# KeyBesselEsquematico.net
KiCad netlist of a schematic drawn in Altium Designer
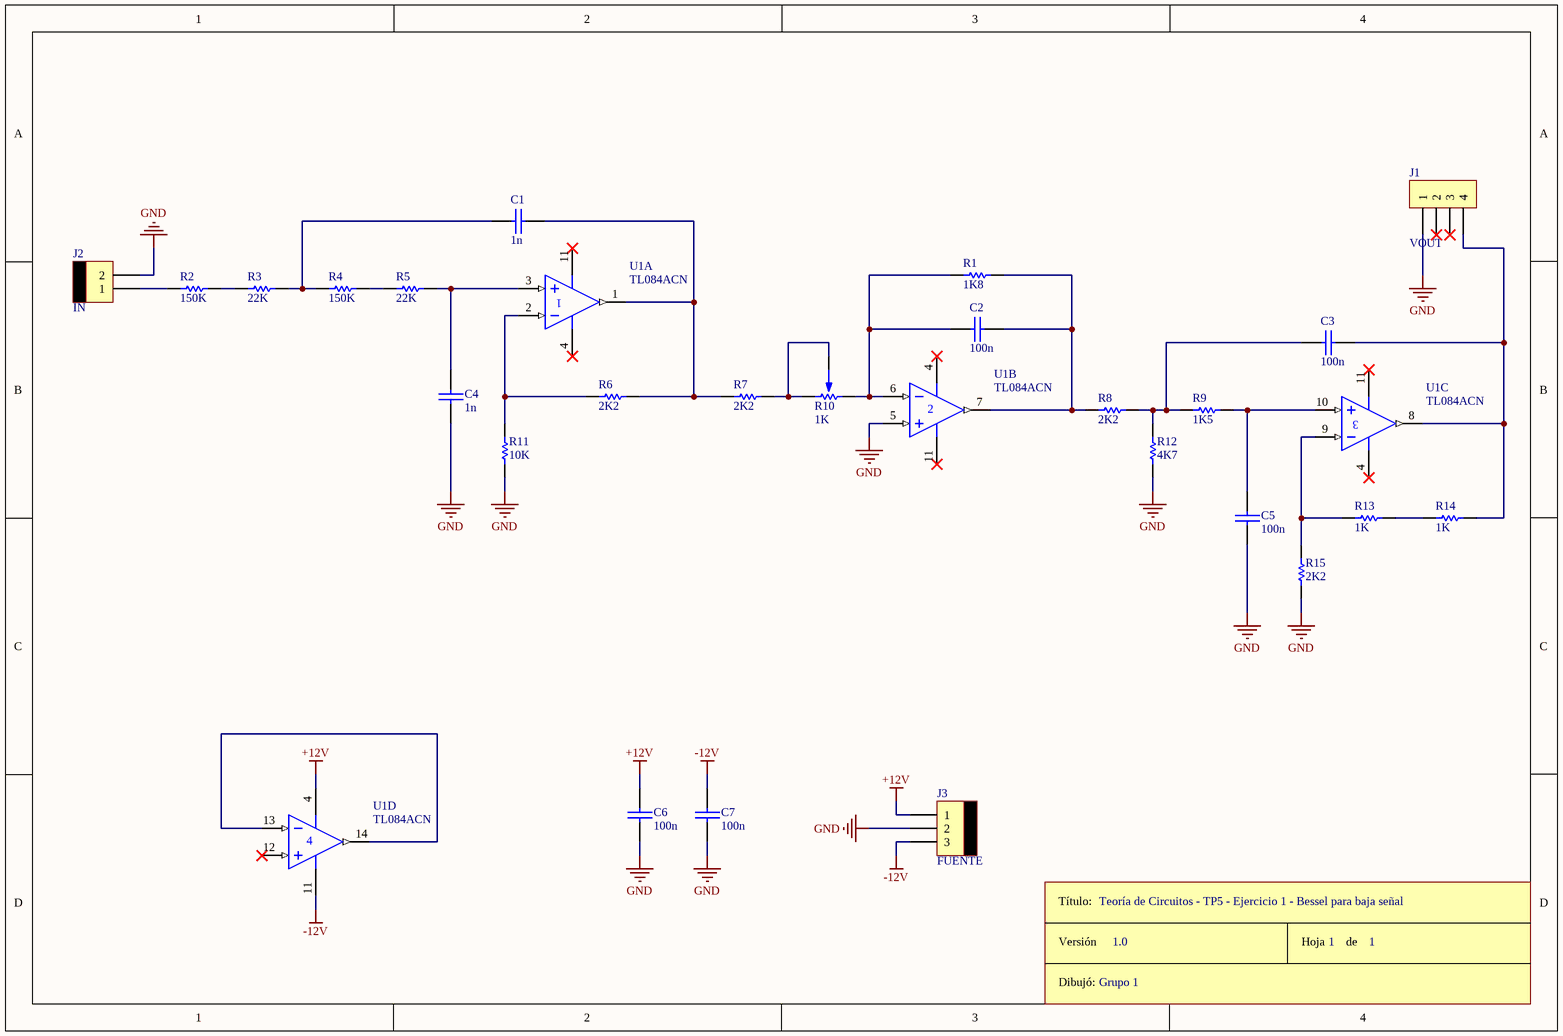
[diagram p0: KeyBesselEsquematico.SchDoc]

(export (version "E")
  (design (tool "Eeschema 10.0.6"))
  (components
    (comp (ref "C1") (value "1n") (footprint "CAP100") (libsource (lib "LIBEBAL") (part "CAP")))
    (comp (ref "C2") (value "100n") (footprint "CAP100") (libsource (lib "LIBEBAL") (part "CAP")))
    (comp (ref "C3") (value "100n") (footprint "CAP100") (libsource (lib "LIBEBAL") (part "CAP")))
    (comp (ref "C4") (value "1n") (footprint "CAP100") (libsource (lib "LIBEBAL") (part "CAP")))
    (comp (ref "C5") (value "100n") (footprint "CAP100") (libsource (lib "LIBEBAL") (part "CAP")))
    (comp (ref "C6") (value "100n") (footprint "CAP100") (libsource (lib "LIBEBAL") (part "CAP")))
    (comp (ref "C7") (value "100n") (footprint "CAP100") (libsource (lib "LIBEBAL") (part "CAP")))
    (comp (ref "J1") (value "VOUT") (footprint "SIP4") (libsource (lib "LIBEBAL") (part "CON4")))
    (comp (ref "J2") (value "IN") (footprint "MOLEX2") (libsource (lib "LIBEBAL") (part "MOLEX2")))
    (comp (ref "J3") (value "FUENTE") (footprint "MOLEX3") (libsource (lib "LIBEBAL") (part "MOLEX3")))
    (comp (ref "R1") (value "1K8") (footprint "RES300") (libsource (lib "LIBEBAL") (part "RES")))
    (comp (ref "R2") (value "150K") (footprint "RES300") (libsource (lib "LIBEBAL") (part "RES")))
    (comp (ref "R3") (value "22K") (footprint "RES300") (libsource (lib "LIBEBAL") (part "RES")))
    (comp (ref "R4") (value "150K") (footprint "RES300") (libsource (lib "LIBEBAL") (part "RES")))
    (comp (ref "R5") (value "22K") (footprint "RES300") (libsource (lib "LIBEBAL") (part "RES")))
    (comp (ref "R6") (value "2K2") (footprint "RES300") (libsource (lib "LIBEBAL") (part "RES")))
    (comp (ref "R7") (value "2K2") (footprint "RES300") (libsource (lib "LIBEBAL") (part "RES")))
    (comp (ref "R8") (value "2K2") (footprint "RES300") (libsource (lib "LIBEBAL") (part "RES")))
    (comp (ref "R9") (value "1K5") (footprint "RES300") (libsource (lib "LIBEBAL") (part "RES")))
    (comp (ref "R10") (value "1K") (footprint "PRESET V") (libsource (lib "LIBEBAL") (part "PRESET")))
    (comp (ref "R11") (value "10K") (footprint "RES300") (libsource (lib "LIBEBAL") (part "RES")))
    (comp (ref "R12") (value "4K7") (footprint "RES300") (libsource (lib "LIBEBAL") (part "RES")))
    (comp (ref "R13") (value "1K") (footprint "RES300") (libsource (lib "LIBEBAL") (part "RES")))
    (comp (ref "R14") (value "1K") (footprint "RES300") (libsource (lib "LIBEBAL") (part "RES")))
    (comp (ref "R15") (value "2K2") (footprint "RES300") (libsource (lib "LIBEBAL") (part "RES")))
    (comp (ref "ROT1") (value "Rótulo") (libsource (lib "LIB PIO IX") (part "Rótulo")))
    (comp (ref "U1")
      (value "TL084ACN")
      (footprint "646-06")
      (description "JFET-Input Operational Amplifier")
      (fields (field (name "PUBLISHER") "Altium Limited"))
      (libsource (lib "Motorola Amplifier Operational Amplifier") (part "TL084ACN"))
    )
  )
  (nets
    (net (code "1") (name "+12V") (class "Default")
      (node (ref "C6") (pin "1") (pinfunction "1_1") (pintype "passive"))
      (node (ref "J3") (pin "1") (pinfunction "1_1") (pintype "passive"))
      (node (ref "U1") (pin "4") (pinfunction "V+_4") (pintype "power_in"))
    )
    (net (code "2") (name "-12V") (class "Default")
      (node (ref "C7") (pin "1") (pinfunction "1_1") (pintype "passive"))
      (node (ref "J3") (pin "3") (pinfunction "3_3") (pintype "passive"))
      (node (ref "U1") (pin "11") (pinfunction "V-_11") (pintype "power_in"))
    )
    (net (code "3") (name "GND") (class "Default")
      (node (ref "C4") (pin "2") (pinfunction "2_2") (pintype "passive"))
      (node (ref "C5") (pin "2") (pinfunction "2_2") (pintype "passive"))
      (node (ref "C6") (pin "2") (pinfunction "2_2") (pintype "passive"))
      (node (ref "C7") (pin "2") (pinfunction "2_2") (pintype "passive"))
      (node (ref "J1") (pin "1") (pinfunction "1_1") (pintype "passive"))
      (node (ref "J2") (pin "2") (pinfunction "2_2") (pintype "passive"))
      (node (ref "J3") (pin "2") (pinfunction "2_2") (pintype "passive"))
      (node (ref "R11") (pin "1") (pinfunction "1_1") (pintype "passive"))
      (node (ref "R12") (pin "1") (pinfunction "1_1") (pintype "passive"))
      (node (ref "R15") (pin "1") (pinfunction "1_1") (pintype "passive"))
      (node (ref "U1") (pin "5") (pinfunction "IN+_5") (pintype "input"))
    )
    (net (code "4") (name "Net-(C1-Pad1)") (class "Default")
      (node (ref "C1") (pin "1") (pinfunction "1_1") (pintype "passive"))
      (node (ref "R3") (pin "2") (pinfunction "2_2") (pintype "passive"))
      (node (ref "R4") (pin "1") (pinfunction "1_1") (pintype "passive"))
    )
    (net (code "5") (name "Net-(C3-Pad1)") (class "Default")
      (node (ref "C3") (pin "1") (pinfunction "1_1") (pintype "passive"))
      (node (ref "R12") (pin "2") (pinfunction "2_2") (pintype "passive"))
      (node (ref "R8") (pin "2") (pinfunction "2_2") (pintype "passive"))
      (node (ref "R9") (pin "1") (pinfunction "1_1") (pintype "passive"))
    )
    (net (code "6") (name "Net-(J2-Pad1)") (class "Default")
      (node (ref "J2") (pin "1") (pinfunction "1_1") (pintype "passive"))
      (node (ref "R2") (pin "1") (pinfunction "1_1") (pintype "passive"))
    )
    (net (code "7") (name "Net-(R2-Pad2)") (class "Default")
      (node (ref "R2") (pin "2") (pinfunction "2_2") (pintype "passive"))
      (node (ref "R3") (pin "1") (pinfunction "1_1") (pintype "passive"))
    )
    (net (code "8") (name "Net-(R4-Pad2)") (class "Default")
      (node (ref "R4") (pin "2") (pinfunction "2_2") (pintype "passive"))
      (node (ref "R5") (pin "1") (pinfunction "1_1") (pintype "passive"))
    )
    (net (code "9") (name "Net-(R10-Pad1)") (class "Default")
      (node (ref "R10") (pin "1") (pinfunction "1_1") (pintype "passive"))
      (node (ref "R10") (pin "2") (pinfunction "2_2") (pintype "passive"))
      (node (ref "R7") (pin "2") (pinfunction "2_2") (pintype "passive"))
    )
    (net (code "10") (name "Net-(R13-Pad2)") (class "Default")
      (node (ref "R13") (pin "2") (pinfunction "2_2") (pintype "passive"))
      (node (ref "R14") (pin "1") (pinfunction "1_1") (pintype "passive"))
    )
    (net (code "11") (name "Net-(U1A-IN+)") (class "Default")
      (node (ref "C4") (pin "1") (pinfunction "1_1") (pintype "passive"))
      (node (ref "R5") (pin "2") (pinfunction "2_2") (pintype "passive"))
      (node (ref "U1") (pin "3") (pinfunction "IN+_3") (pintype "input"))
    )
    (net (code "12") (name "Net-(U1A-IN-)") (class "Default")
      (node (ref "R11") (pin "2") (pinfunction "2_2") (pintype "passive"))
      (node (ref "R6") (pin "1") (pinfunction "1_1") (pintype "passive"))
      (node (ref "U1") (pin "2") (pinfunction "IN-_2") (pintype "input"))
    )
    (net (code "13") (name "Net-(U1A-OUT)") (class "Default")
      (node (ref "C1") (pin "2") (pinfunction "2_2") (pintype "passive"))
      (node (ref "R6") (pin "2") (pinfunction "2_2") (pintype "passive"))
      (node (ref "R7") (pin "1") (pinfunction "1_1") (pintype "passive"))
      (node (ref "U1") (pin "1") (pinfunction "OUT_1") (pintype "output"))
    )
    (net (code "14") (name "Net-(U1B-IN-)") (class "Default")
      (node (ref "C2") (pin "1") (pinfunction "1_1") (pintype "passive"))
      (node (ref "R1") (pin "1") (pinfunction "1_1") (pintype "passive"))
      (node (ref "R10") (pin "3") (pinfunction "3_3") (pintype "passive"))
      (node (ref "U1") (pin "6") (pinfunction "IN-_6") (pintype "input"))
    )
    (net (code "15") (name "Net-(U1B-OUT)") (class "Default")
      (node (ref "C2") (pin "2") (pinfunction "2_2") (pintype "passive"))
      (node (ref "R1") (pin "2") (pinfunction "2_2") (pintype "passive"))
      (node (ref "R8") (pin "1") (pinfunction "1_1") (pintype "passive"))
      (node (ref "U1") (pin "7") (pinfunction "OUT_7") (pintype "output"))
    )
    (net (code "16") (name "Net-(U1C-IN+)") (class "Default")
      (node (ref "C5") (pin "1") (pinfunction "1_1") (pintype "passive"))
      (node (ref "R9") (pin "2") (pinfunction "2_2") (pintype "passive"))
      (node (ref "U1") (pin "10") (pinfunction "IN+_10") (pintype "input"))
    )
    (net (code "17") (name "Net-(U1C-IN-)") (class "Default")
      (node (ref "R13") (pin "1") (pinfunction "1_1") (pintype "passive"))
      (node (ref "R15") (pin "2") (pinfunction "2_2") (pintype "passive"))
      (node (ref "U1") (pin "9") (pinfunction "IN-_9") (pintype "input"))
    )
    (net (code "18") (name "Net-(U1C-OUT)") (class "Default")
      (node (ref "C3") (pin "2") (pinfunction "2_2") (pintype "passive"))
      (node (ref "J1") (pin "4") (pinfunction "4_4") (pintype "passive"))
      (node (ref "R14") (pin "2") (pinfunction "2_2") (pintype "passive"))
      (node (ref "U1") (pin "8") (pinfunction "OUT_8") (pintype "output"))
    )
    (net (code "19") (name "Net-(U1D-IN-)") (class "Default")
      (node (ref "U1") (pin "13") (pinfunction "IN-_13") (pintype "input"))
      (node (ref "U1") (pin "14") (pinfunction "OUT_14") (pintype "output"))
    )
    (net (code "20") (name "unconnected-(J1-Pad2)") (class "Default")
      (node (ref "J1") (pin "2") (pinfunction "2_2") (pintype "passive+no_connect"))
    )
    (net (code "21") (name "unconnected-(J1-Pad3)") (class "Default")
      (node (ref "J1") (pin "3") (pinfunction "3_3") (pintype "passive+no_connect"))
    )
    (net (code "22") (name "unconnected-(U1A-V+-Pad4)") (class "Default")
      (node (ref "U1") (pin "4") (pinfunction "V+_4") (pintype "power_in+no_connect"))
    )
    (net (code "23") (name "unconnected-(U1A-V--Pad11)") (class "Default")
      (node (ref "U1") (pin "11") (pinfunction "V-_11") (pintype "power_in+no_connect"))
    )
    (net (code "24") (name "unconnected-(U1B-V+-Pad4)") (class "Default")
      (node (ref "U1") (pin "4") (pinfunction "V+_4") (pintype "power_in+no_connect"))
    )
    (net (code "25") (name "unconnected-(U1B-V--Pad11)") (class "Default")
      (node (ref "U1") (pin "11") (pinfunction "V-_11") (pintype "power_in+no_connect"))
    )
    (net (code "26") (name "unconnected-(U1C-V+-Pad4)") (class "Default")
      (node (ref "U1") (pin "4") (pinfunction "V+_4") (pintype "power_in+no_connect"))
    )
    (net (code "27") (name "unconnected-(U1C-V--Pad11)") (class "Default")
      (node (ref "U1") (pin "11") (pinfunction "V-_11") (pintype "power_in+no_connect"))
    )
    (net (code "28") (name "unconnected-(U1D-IN+-Pad12)") (class "Default")
      (node (ref "U1") (pin "12") (pinfunction "IN+_12") (pintype "input+no_connect"))
    )
  )
)
